# tpms_breakout.net
KiCad netlist of a schematic drawn in EAGLE
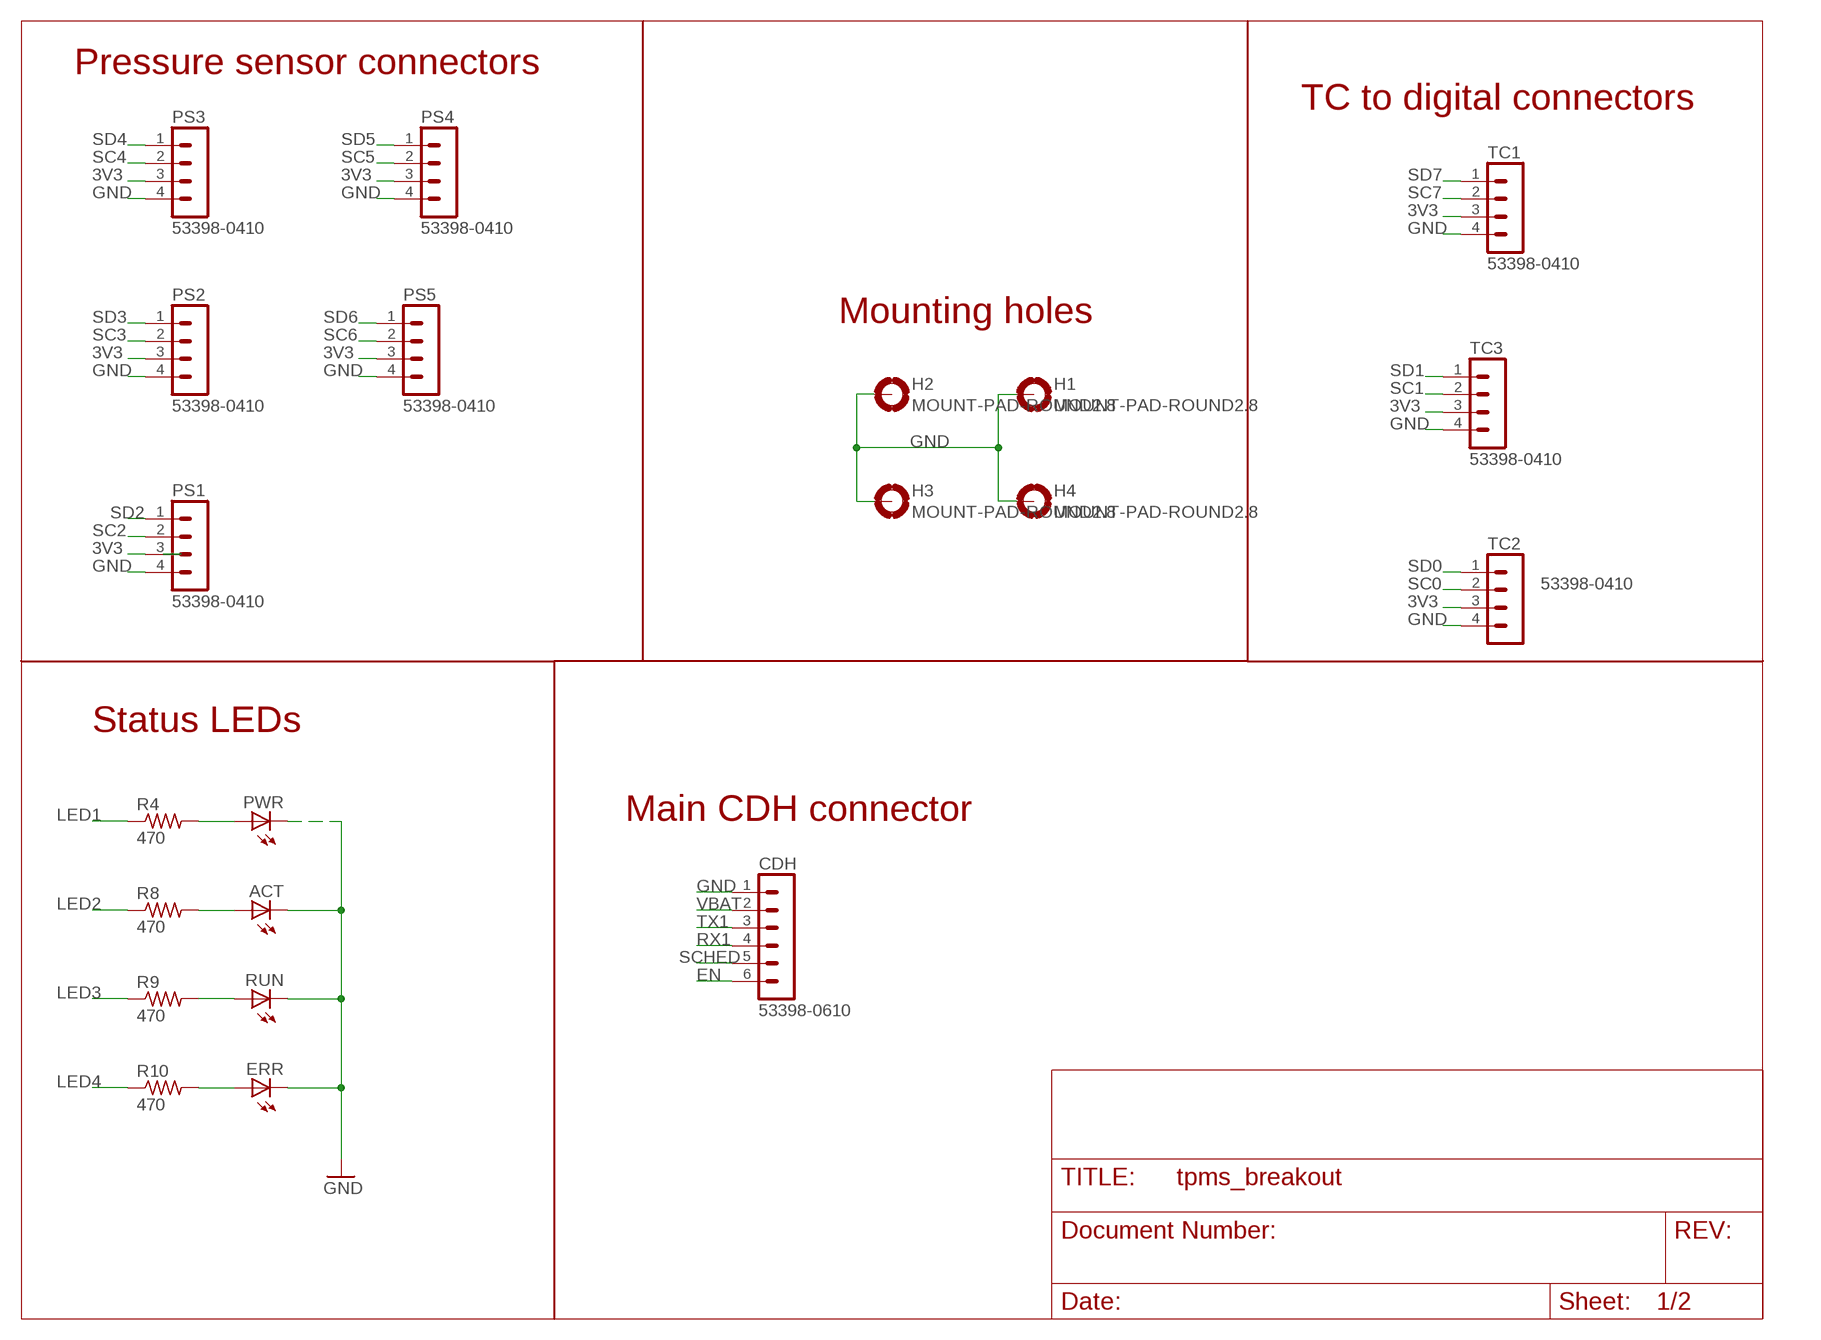
[diagram p0: schematic, sheet 1]
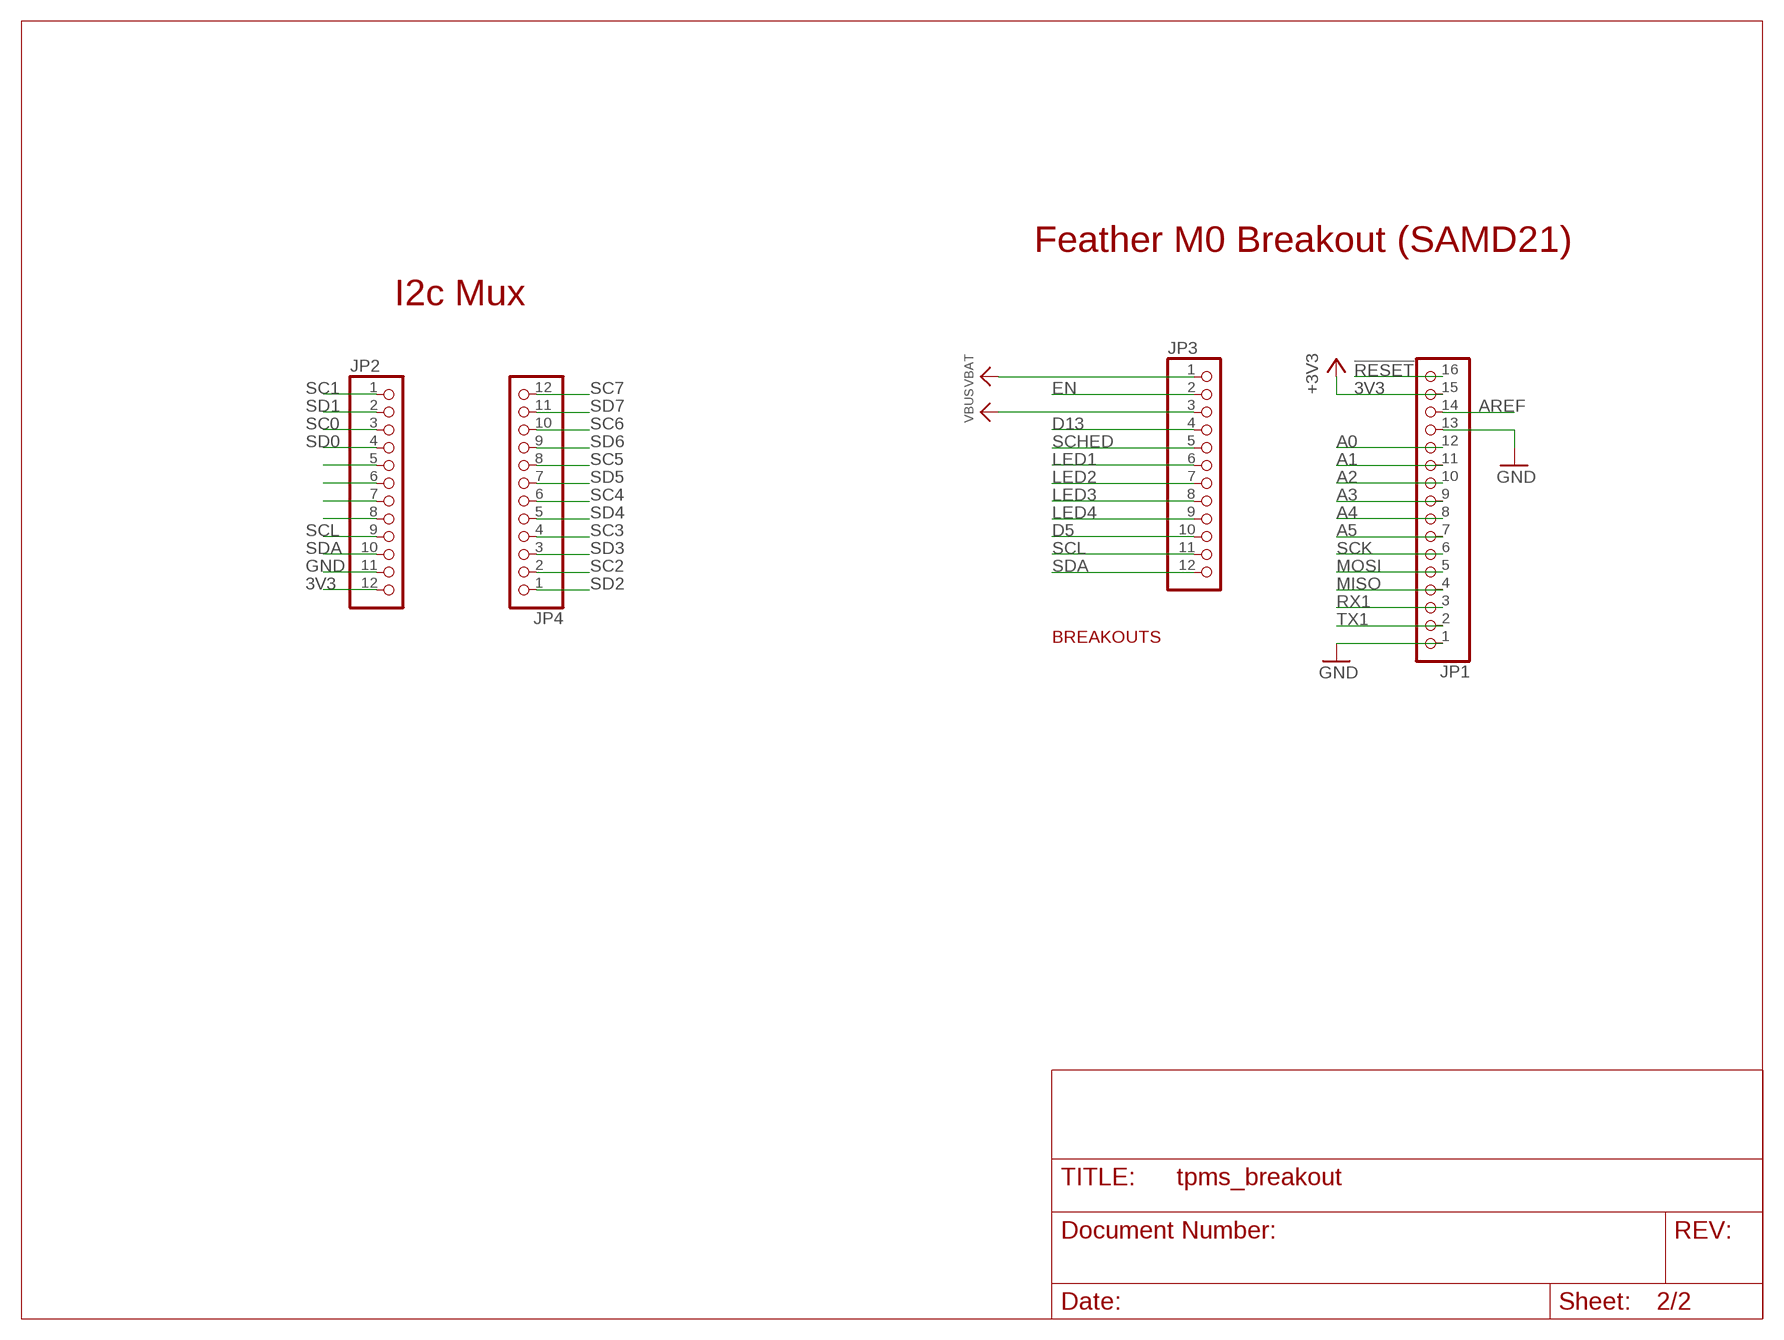
[diagram p1: schematic, sheet 2]

(export (version "E")
  (design (tool "Eeschema 10.0.6"))
  (components
    (comp (ref "JP1")
      (value "HEADER-1X16ROUND")
      (footprint "eagle-import:1X16_ROUND")
      (libsource (lib "eagle-import") (part "HEADER-1X16ROUND"))
    )
    (comp (ref "JP2")
      (value "HEADER-1X12")
      (footprint "eagle-import:1X12_ROUND")
      (libsource (lib "eagle-import") (part "HEADER-1X12"))
    )
    (comp (ref "JP3")
      (value "HEADER-1X12")
      (footprint "eagle-import:1X12_ROUND")
      (libsource (lib "eagle-import") (part "HEADER-1X12"))
    )
    (comp (ref "JP4")
      (value "HEADER-1X12")
      (footprint "eagle-import:1X12_ROUND")
      (libsource (lib "eagle-import") (part "HEADER-1X12"))
    )
    (comp (ref "ACT")
      (value "LEDCHIP-LED0603")
      (footprint "eagle-import:CHIP-LED0603")
      (libsource (lib "eagle-import") (part "LEDCHIP-LED0603"))
    )
    (comp (ref "CDH")
      (value "53398-0610")
      (footprint "eagle-import:53398-0610")
      (libsource (lib "eagle-import") (part "53398-0610"))
    )
    (comp (ref "ERR")
      (value "LEDCHIP-LED0603")
      (footprint "eagle-import:CHIP-LED0603")
      (libsource (lib "eagle-import") (part "LEDCHIP-LED0603"))
    )
    (comp (ref "H1")
      (value "MOUNT-PAD-ROUND2.8")
      (footprint "eagle-import:2,8-PAD")
      (libsource (lib "eagle-import") (part "MOUNT-PAD-ROUND2.8"))
    )
    (comp (ref "H2")
      (value "MOUNT-PAD-ROUND2.8")
      (footprint "eagle-import:2,8-PAD")
      (libsource (lib "eagle-import") (part "MOUNT-PAD-ROUND2.8"))
    )
    (comp (ref "H3")
      (value "MOUNT-PAD-ROUND2.8")
      (footprint "eagle-import:2,8-PAD")
      (libsource (lib "eagle-import") (part "MOUNT-PAD-ROUND2.8"))
    )
    (comp (ref "H4")
      (value "MOUNT-PAD-ROUND2.8")
      (footprint "eagle-import:2,8-PAD")
      (libsource (lib "eagle-import") (part "MOUNT-PAD-ROUND2.8"))
    )
    (comp (ref "PS1")
      (value "53398-0410")
      (footprint "eagle-import:53398-0410")
      (libsource (lib "eagle-import") (part "53398-0410"))
    )
    (comp (ref "PS2")
      (value "53398-0410")
      (footprint "eagle-import:53398-0410")
      (libsource (lib "eagle-import") (part "53398-0410"))
    )
    (comp (ref "PS3")
      (value "53398-0410")
      (footprint "eagle-import:53398-0410")
      (libsource (lib "eagle-import") (part "53398-0410"))
    )
    (comp (ref "PS4")
      (value "53398-0410")
      (footprint "eagle-import:53398-0410")
      (libsource (lib "eagle-import") (part "53398-0410"))
    )
    (comp (ref "PS5")
      (value "53398-0410")
      (footprint "eagle-import:53398-0410")
      (libsource (lib "eagle-import") (part "53398-0410"))
    )
    (comp (ref "PWR")
      (value "LEDCHIP-LED0603")
      (footprint "eagle-import:CHIP-LED0603")
      (libsource (lib "eagle-import") (part "LEDCHIP-LED0603"))
    )
    (comp (ref "R4")
      (value "470")
      (footprint "eagle-import:R0603")
      (libsource (lib "eagle-import") (part "R-US_R0603"))
    )
    (comp (ref "R8")
      (value "470")
      (footprint "eagle-import:R0603")
      (libsource (lib "eagle-import") (part "R-US_R0603"))
    )
    (comp (ref "R9")
      (value "470")
      (footprint "eagle-import:R0603")
      (libsource (lib "eagle-import") (part "R-US_R0603"))
    )
    (comp (ref "R10")
      (value "470")
      (footprint "eagle-import:R0603")
      (libsource (lib "eagle-import") (part "R-US_R0603"))
    )
    (comp (ref "RUN")
      (value "LEDCHIP-LED0603")
      (footprint "eagle-import:CHIP-LED0603")
      (libsource (lib "eagle-import") (part "LEDCHIP-LED0603"))
    )
    (comp (ref "TC1")
      (value "53398-0410")
      (footprint "eagle-import:53398-0410")
      (libsource (lib "eagle-import") (part "53398-0410"))
    )
    (comp (ref "TC2")
      (value "53398-0410")
      (footprint "eagle-import:53398-0410")
      (libsource (lib "eagle-import") (part "53398-0410"))
    )
    (comp (ref "TC3")
      (value "53398-0410")
      (footprint "eagle-import:53398-0410")
      (libsource (lib "eagle-import") (part "53398-0410"))
    )
  )
  (nets
    (net (code "1") (name "3V3") (class "Default")
      (node (ref "JP1") (pin "15") (pinfunction "15_15") (pintype "passive"))
      (node (ref "JP2") (pin "12") (pinfunction "12_12") (pintype "passive"))
      (node (ref "PS1") (pin "3") (pinfunction "3_3") (pintype "passive"))
      (node (ref "PS2") (pin "3") (pinfunction "3_3") (pintype "passive"))
      (node (ref "PS3") (pin "3") (pinfunction "3_3") (pintype "passive"))
      (node (ref "PS4") (pin "3") (pinfunction "3_3") (pintype "passive"))
      (node (ref "PS5") (pin "3") (pinfunction "3_3") (pintype "passive"))
      (node (ref "TC1") (pin "3") (pinfunction "3_3") (pintype "passive"))
      (node (ref "TC2") (pin "3") (pinfunction "3_3") (pintype "passive"))
      (node (ref "TC3") (pin "3") (pinfunction "3_3") (pintype "passive"))
    )
    (net (code "2") (name "A0") (class "Default")
      (node (ref "JP1") (pin "12") (pinfunction "12_12") (pintype "passive"))
    )
    (net (code "3") (name "A1") (class "Default")
      (node (ref "JP1") (pin "11") (pinfunction "11_11") (pintype "passive"))
    )
    (net (code "4") (name "A2") (class "Default")
      (node (ref "JP1") (pin "10") (pinfunction "10_10") (pintype "passive"))
    )
    (net (code "5") (name "A3") (class "Default")
      (node (ref "JP1") (pin "9") (pinfunction "9_9") (pintype "passive"))
    )
    (net (code "6") (name "A4") (class "Default")
      (node (ref "JP1") (pin "8") (pinfunction "8_8") (pintype "passive"))
    )
    (net (code "7") (name "A5") (class "Default")
      (node (ref "JP1") (pin "7") (pinfunction "7_7") (pintype "passive"))
    )
    (net (code "8") (name "AREF") (class "Default")
      (node (ref "JP1") (pin "14") (pinfunction "14_14") (pintype "passive"))
    )
    (net (code "9") (name "D5") (class "Default")
      (node (ref "JP3") (pin "10") (pinfunction "10_10") (pintype "passive"))
    )
    (net (code "10") (name "D13") (class "Default")
      (node (ref "JP3") (pin "4") (pinfunction "4_4") (pintype "passive"))
    )
    (net (code "11") (name "EN") (class "Default")
      (node (ref "CDH") (pin "6") (pinfunction "6_6") (pintype "passive"))
      (node (ref "JP3") (pin "2") (pinfunction "2_2") (pintype "passive"))
    )
    (net (code "12") (name "GND") (class "Default")
      (node (ref "ACT") (pin "C") (pinfunction "C_C") (pintype "passive"))
      (node (ref "CDH") (pin "1") (pinfunction "1_1") (pintype "passive"))
      (node (ref "ERR") (pin "C") (pinfunction "C_C") (pintype "passive"))
      (node (ref "H1") (pin "B2,8") (pinfunction "MOUNT_B2,8") (pintype "passive"))
      (node (ref "H2") (pin "B2,8") (pinfunction "MOUNT_B2,8") (pintype "passive"))
      (node (ref "H3") (pin "B2,8") (pinfunction "MOUNT_B2,8") (pintype "passive"))
      (node (ref "H4") (pin "B2,8") (pinfunction "MOUNT_B2,8") (pintype "passive"))
      (node (ref "JP1") (pin "1") (pinfunction "1_1") (pintype "passive"))
      (node (ref "JP1") (pin "13") (pinfunction "13_13") (pintype "passive"))
      (node (ref "JP2") (pin "11") (pinfunction "11_11") (pintype "passive"))
      (node (ref "PS1") (pin "4") (pinfunction "4_4") (pintype "passive"))
      (node (ref "PS2") (pin "4") (pinfunction "4_4") (pintype "passive"))
      (node (ref "PS3") (pin "4") (pinfunction "4_4") (pintype "passive"))
      (node (ref "PS4") (pin "4") (pinfunction "4_4") (pintype "passive"))
      (node (ref "PS5") (pin "4") (pinfunction "4_4") (pintype "passive"))
      (node (ref "PWR") (pin "C") (pinfunction "C_C") (pintype "passive"))
      (node (ref "RUN") (pin "C") (pinfunction "C_C") (pintype "passive"))
      (node (ref "TC1") (pin "4") (pinfunction "4_4") (pintype "passive"))
      (node (ref "TC2") (pin "4") (pinfunction "4_4") (pintype "passive"))
      (node (ref "TC3") (pin "4") (pinfunction "4_4") (pintype "passive"))
    )
    (net (code "13") (name "LED1") (class "Default")
      (node (ref "JP3") (pin "6") (pinfunction "6_6") (pintype "passive"))
      (node (ref "R4") (pin "1") (pinfunction "1_1") (pintype "passive"))
    )
    (net (code "14") (name "LED2") (class "Default")
      (node (ref "JP3") (pin "7") (pinfunction "7_7") (pintype "passive"))
      (node (ref "R8") (pin "1") (pinfunction "1_1") (pintype "passive"))
    )
    (net (code "15") (name "LED3") (class "Default")
      (node (ref "JP3") (pin "8") (pinfunction "8_8") (pintype "passive"))
      (node (ref "R9") (pin "1") (pinfunction "1_1") (pintype "passive"))
    )
    (net (code "16") (name "LED4") (class "Default")
      (node (ref "JP3") (pin "9") (pinfunction "9_9") (pintype "passive"))
      (node (ref "R10") (pin "1") (pinfunction "1_1") (pintype "passive"))
    )
    (net (code "17") (name "MISO") (class "Default")
      (node (ref "JP1") (pin "4") (pinfunction "4_4") (pintype "passive"))
    )
    (net (code "18") (name "MOSI") (class "Default")
      (node (ref "JP1") (pin "5") (pinfunction "5_5") (pintype "passive"))
    )
    (net (code "19") (name "Net-(ACT-PadA)") (class "Default")
      (node (ref "ACT") (pin "A") (pinfunction "A_A") (pintype "passive"))
      (node (ref "R8") (pin "2") (pinfunction "2_2") (pintype "passive"))
    )
    (net (code "20") (name "Net-(ERR-PadA)") (class "Default")
      (node (ref "ERR") (pin "A") (pinfunction "A_A") (pintype "passive"))
      (node (ref "R10") (pin "2") (pinfunction "2_2") (pintype "passive"))
    )
    (net (code "21") (name "Net-(PWR-PadA)") (class "Default")
      (node (ref "PWR") (pin "A") (pinfunction "A_A") (pintype "passive"))
      (node (ref "R4") (pin "2") (pinfunction "2_2") (pintype "passive"))
    )
    (net (code "22") (name "Net-(R9-Pad2)") (class "Default")
      (node (ref "R9") (pin "2") (pinfunction "2_2") (pintype "passive"))
      (node (ref "RUN") (pin "A") (pinfunction "A_A") (pintype "passive"))
    )
    (net (code "23") (name "RX1") (class "Default")
      (node (ref "CDH") (pin "4") (pinfunction "4_4") (pintype "passive"))
      (node (ref "JP1") (pin "3") (pinfunction "3_3") (pintype "passive"))
    )
    (net (code "24") (name "SC0") (class "Default")
      (node (ref "JP2") (pin "3") (pinfunction "3_3") (pintype "passive"))
      (node (ref "TC2") (pin "2") (pinfunction "2_2") (pintype "passive"))
    )
    (net (code "25") (name "SC1") (class "Default")
      (node (ref "JP2") (pin "1") (pinfunction "1_1") (pintype "passive"))
      (node (ref "TC3") (pin "2") (pinfunction "2_2") (pintype "passive"))
    )
    (net (code "26") (name "SC2") (class "Default")
      (node (ref "JP4") (pin "2") (pinfunction "2_2") (pintype "passive"))
      (node (ref "PS1") (pin "2") (pinfunction "2_2") (pintype "passive"))
    )
    (net (code "27") (name "SC3") (class "Default")
      (node (ref "JP4") (pin "4") (pinfunction "4_4") (pintype "passive"))
      (node (ref "PS2") (pin "2") (pinfunction "2_2") (pintype "passive"))
    )
    (net (code "28") (name "SC4") (class "Default")
      (node (ref "JP4") (pin "6") (pinfunction "6_6") (pintype "passive"))
      (node (ref "PS3") (pin "2") (pinfunction "2_2") (pintype "passive"))
    )
    (net (code "29") (name "SC5") (class "Default")
      (node (ref "JP4") (pin "8") (pinfunction "8_8") (pintype "passive"))
      (node (ref "PS4") (pin "2") (pinfunction "2_2") (pintype "passive"))
    )
    (net (code "30") (name "SC6") (class "Default")
      (node (ref "JP4") (pin "10") (pinfunction "10_10") (pintype "passive"))
      (node (ref "PS5") (pin "2") (pinfunction "2_2") (pintype "passive"))
    )
    (net (code "31") (name "SC7") (class "Default")
      (node (ref "JP4") (pin "12") (pinfunction "12_12") (pintype "passive"))
      (node (ref "TC1") (pin "2") (pinfunction "2_2") (pintype "passive"))
    )
    (net (code "32") (name "SCHED") (class "Default")
      (node (ref "CDH") (pin "5") (pinfunction "5_5") (pintype "passive"))
      (node (ref "JP3") (pin "5") (pinfunction "5_5") (pintype "passive"))
    )
    (net (code "33") (name "SCK") (class "Default")
      (node (ref "JP1") (pin "6") (pinfunction "6_6") (pintype "passive"))
    )
    (net (code "34") (name "SCL") (class "Default")
      (node (ref "JP2") (pin "9") (pinfunction "9_9") (pintype "passive"))
      (node (ref "JP3") (pin "11") (pinfunction "11_11") (pintype "passive"))
    )
    (net (code "35") (name "SD0") (class "Default")
      (node (ref "JP2") (pin "4") (pinfunction "4_4") (pintype "passive"))
      (node (ref "TC2") (pin "1") (pinfunction "1_1") (pintype "passive"))
    )
    (net (code "36") (name "SD1") (class "Default")
      (node (ref "JP2") (pin "2") (pinfunction "2_2") (pintype "passive"))
      (node (ref "TC3") (pin "1") (pinfunction "1_1") (pintype "passive"))
    )
    (net (code "37") (name "SD2") (class "Default")
      (node (ref "JP4") (pin "1") (pinfunction "1_1") (pintype "passive"))
      (node (ref "PS1") (pin "1") (pinfunction "1_1") (pintype "passive"))
    )
    (net (code "38") (name "SD3") (class "Default")
      (node (ref "JP4") (pin "3") (pinfunction "3_3") (pintype "passive"))
      (node (ref "PS2") (pin "1") (pinfunction "1_1") (pintype "passive"))
    )
    (net (code "39") (name "SD4") (class "Default")
      (node (ref "JP4") (pin "5") (pinfunction "5_5") (pintype "passive"))
      (node (ref "PS3") (pin "1") (pinfunction "1_1") (pintype "passive"))
    )
    (net (code "40") (name "SD5") (class "Default")
      (node (ref "JP4") (pin "7") (pinfunction "7_7") (pintype "passive"))
      (node (ref "PS4") (pin "1") (pinfunction "1_1") (pintype "passive"))
    )
    (net (code "41") (name "SD6") (class "Default")
      (node (ref "JP4") (pin "9") (pinfunction "9_9") (pintype "passive"))
      (node (ref "PS5") (pin "1") (pinfunction "1_1") (pintype "passive"))
    )
    (net (code "42") (name "SD7") (class "Default")
      (node (ref "JP4") (pin "11") (pinfunction "11_11") (pintype "passive"))
      (node (ref "TC1") (pin "1") (pinfunction "1_1") (pintype "passive"))
    )
    (net (code "43") (name "SDA") (class "Default")
      (node (ref "JP2") (pin "10") (pinfunction "10_10") (pintype "passive"))
      (node (ref "JP3") (pin "12") (pinfunction "12_12") (pintype "passive"))
    )
    (net (code "44") (name "TX1") (class "Default")
      (node (ref "CDH") (pin "3") (pinfunction "3_3") (pintype "passive"))
      (node (ref "JP1") (pin "2") (pinfunction "2_2") (pintype "passive"))
    )
    (net (code "45") (name "VBAT") (class "Default")
      (node (ref "CDH") (pin "2") (pinfunction "2_2") (pintype "passive"))
      (node (ref "JP3") (pin "1") (pinfunction "1_1") (pintype "passive"))
    )
    (net (code "46") (name "VBUS") (class "Default")
      (node (ref "JP3") (pin "3") (pinfunction "3_3") (pintype "passive"))
    )
    (net (code "47") (name "unconnected-(JP2-Pad5)") (class "Default")
      (node (ref "JP2") (pin "5") (pinfunction "5_5") (pintype "passive"))
    )
    (net (code "48") (name "unconnected-(JP2-Pad6)") (class "Default")
      (node (ref "JP2") (pin "6") (pinfunction "6_6") (pintype "passive"))
    )
    (net (code "49") (name "unconnected-(JP2-Pad7)") (class "Default")
      (node (ref "JP2") (pin "7") (pinfunction "7_7") (pintype "passive"))
    )
    (net (code "50") (name "unconnected-(JP2-Pad8)") (class "Default")
      (node (ref "JP2") (pin "8") (pinfunction "8_8") (pintype "passive"))
    )
    (net (code "51") (name "~{RESET}") (class "Default")
      (node (ref "JP1") (pin "16") (pinfunction "16_16") (pintype "passive"))
    )
  )
)
